# MCU_Control.net
KiCad netlist of a schematic drawn in Altium Designer
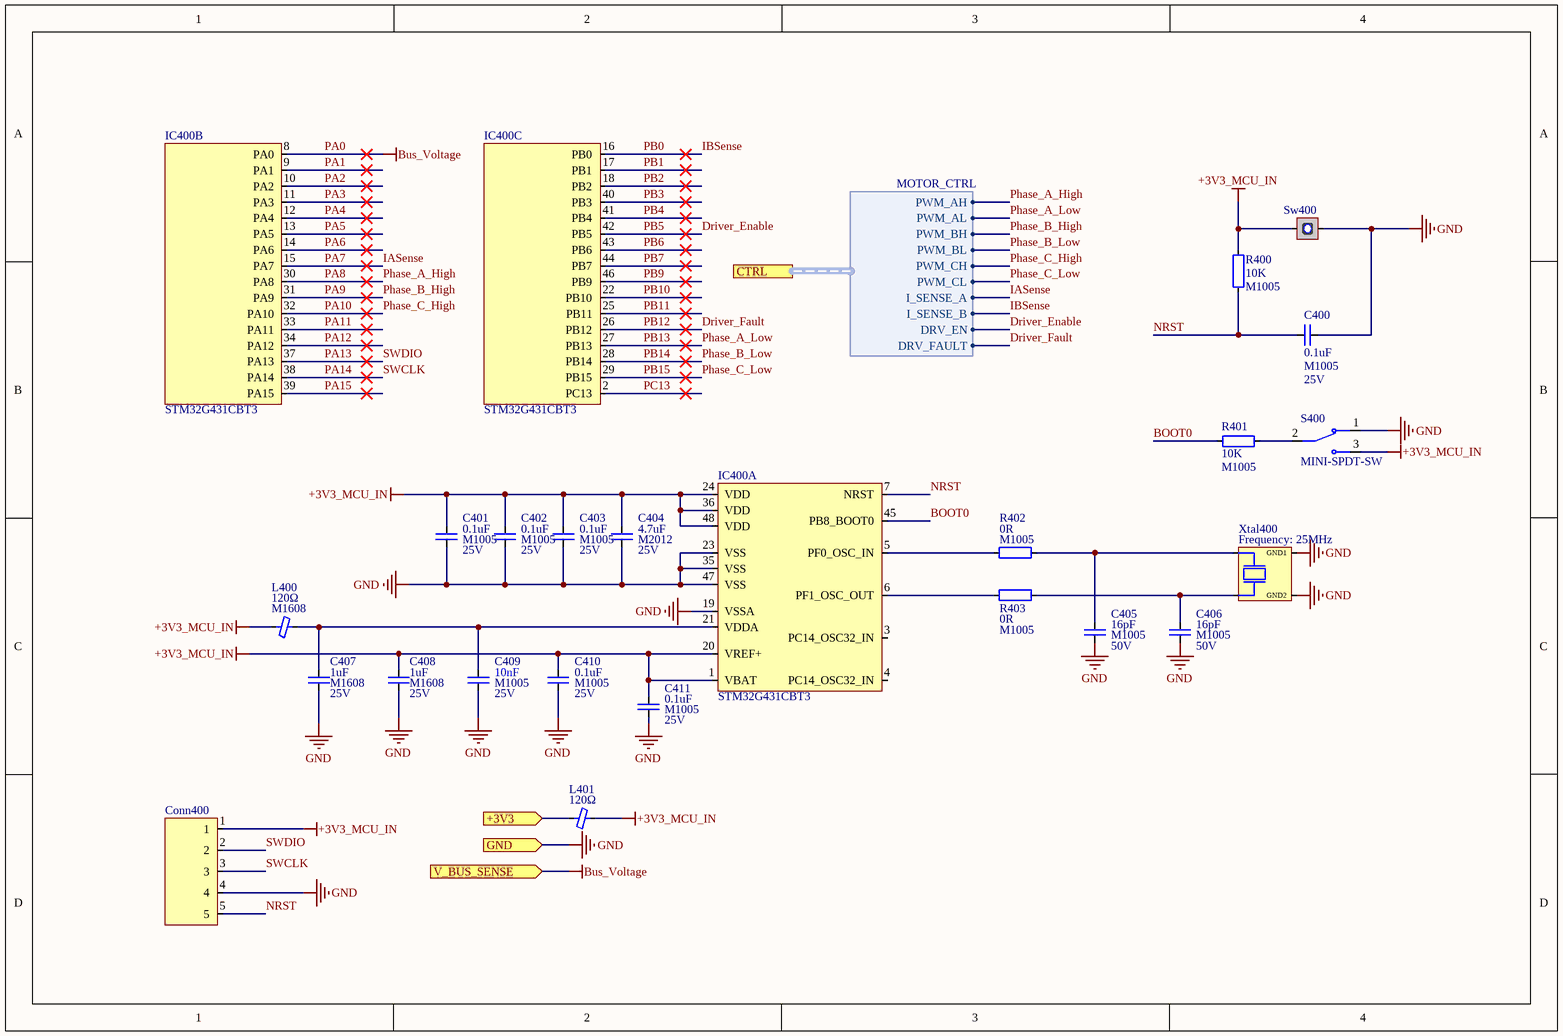
[diagram p0: MCU_Control.SchDoc]

(export (version "E")
  (design (tool "Eeschema 10.0.6"))
  (components
    (comp (ref "C400")
      (value "0.1uF")
      (footprint "Capacitor_Seramic_M1005_I0402")
      (description "Cap, Cer, 0.1uF, 25V, M1005")
      (fields
        (field (name "TOLERANCE") "±10%")
        (field (name "MANUFACTURER PART NUMBER") "CC0402KRX7R8BB104")
        (field (name "PACKAGE") "M1005")
        (field (name "RATED VOLTAGE") "25V")
      )
      (libsource (lib "Capacitor") (part "Capacitor_Seramic"))
    )
    (comp (ref "C401")
      (value "0.1uF")
      (footprint "Capacitor_Seramic_M1005_I0402")
      (description "Cap, Cer, 0.1uF, 25V, M1005")
      (fields
        (field (name "TOLERANCE") "±10%")
        (field (name "MANUFACTURER PART NUMBER") "CC0402KRX7R8BB104")
        (field (name "PACKAGE") "M1005")
        (field (name "RATED VOLTAGE") "25V")
      )
      (libsource (lib "Capacitor") (part "Capacitor_Seramic"))
    )
    (comp (ref "C402")
      (value "0.1uF")
      (footprint "Capacitor_Seramic_M1005_I0402")
      (description "Cap, Cer, 0.1uF, 25V, M1005")
      (fields
        (field (name "TOLERANCE") "±10%")
        (field (name "MANUFACTURER PART NUMBER") "CC0402KRX7R8BB104")
        (field (name "PACKAGE") "M1005")
        (field (name "RATED VOLTAGE") "25V")
      )
      (libsource (lib "Capacitor") (part "Capacitor_Seramic"))
    )
    (comp (ref "C403")
      (value "0.1uF")
      (footprint "Capacitor_Seramic_M1005_I0402")
      (description "Cap, Cer, 0.1uF, 25V, M1005")
      (fields
        (field (name "TOLERANCE") "±10%")
        (field (name "MANUFACTURER PART NUMBER") "CC0402KRX7R8BB104")
        (field (name "PACKAGE") "M1005")
        (field (name "RATED VOLTAGE") "25V")
      )
      (libsource (lib "Capacitor") (part "Capacitor_Seramic"))
    )
    (comp (ref "C404")
      (value "4.7uF")
      (footprint "Capacitor_Seramic_M2012_I0805")
      (description "Cap, Cer, 4.7uF, 25V, M2012")
      (fields
        (field (name "TOLERANCE") "±10%")
        (field (name "MANUFACTURER PART NUMBER") "C2012X7R1E475K125AB")
        (field (name "PACKAGE") "M2012")
        (field (name "RATED VOLTAGE") "25V")
      )
      (libsource (lib "Capacitor") (part "Capacitor_Seramic"))
    )
    (comp (ref "C405")
      (value "16pF")
      (footprint "Capacitor_Seramic_M1005_I0402")
      (description "Cap, Cer, 16pF, 50V, M1005")
      (fields
        (field (name "TOLERANCE") "5%")
        (field (name "MANUFACTURER PART NUMBER") "0402N160J500CT")
        (field (name "PACKAGE") "M1005")
        (field (name "RATED VOLTAGE") "50V")
      )
      (libsource (lib "Capacitor") (part "Capacitor_Seramic"))
    )
    (comp (ref "C406")
      (value "16pF")
      (footprint "Capacitor_Seramic_M1005_I0402")
      (description "Cap, Cer, 16pF, 50V, M1005")
      (fields
        (field (name "TOLERANCE") "5%")
        (field (name "MANUFACTURER PART NUMBER") "0402N160J500CT")
        (field (name "PACKAGE") "M1005")
        (field (name "RATED VOLTAGE") "50V")
      )
      (libsource (lib "Capacitor") (part "Capacitor_Seramic"))
    )
    (comp (ref "C407")
      (value "1uF")
      (footprint "Capacitor_Seramic_M1608_I0603")
      (description "Cap, Cer, 1uF, 25V, M1608")
      (fields
        (field (name "TOLERANCE") "±10%")
        (field (name "MANUFACTURER PART NUMBER") "C1608X7R1E105K080AB")
        (field (name "PACKAGE") "M1608")
        (field (name "RATED VOLTAGE") "25V")
      )
      (libsource (lib "Capacitor") (part "Capacitor_Seramic"))
    )
    (comp (ref "C408")
      (value "1uF")
      (footprint "Capacitor_Seramic_M1608_I0603")
      (description "Cap, Cer, 1uF, 25V, M1608")
      (fields
        (field (name "TOLERANCE") "±10%")
        (field (name "MANUFACTURER PART NUMBER") "C1608X7R1E105K080AB")
        (field (name "PACKAGE") "M1608")
        (field (name "RATED VOLTAGE") "25V")
      )
      (libsource (lib "Capacitor") (part "Capacitor_Seramic"))
    )
    (comp (ref "C409")
      (value "10nF")
      (footprint "Capacitor_Seramic_M1005_I0402")
      (description "Cap, Cer, 10nF, 25V, M1005")
      (fields
        (field (name "TOLERANCE") "±10%")
        (field (name "MANUFACTURER PART NUMBER") "CC0402KRX7R8BB103")
        (field (name "PACKAGE") "M1005")
        (field (name "RATED VOLTAGE") "25V")
      )
      (libsource (lib "Capacitor") (part "Capacitor_Seramic"))
    )
    (comp (ref "C410")
      (value "0.1uF")
      (footprint "Capacitor_Seramic_M1005_I0402")
      (description "Cap, Cer, 0.1uF, 25V, M1005")
      (fields
        (field (name "TOLERANCE") "±10%")
        (field (name "MANUFACTURER PART NUMBER") "CC0402KRX7R8BB104")
        (field (name "PACKAGE") "M1005")
        (field (name "RATED VOLTAGE") "25V")
      )
      (libsource (lib "Capacitor") (part "Capacitor_Seramic"))
    )
    (comp (ref "C411")
      (value "0.1uF")
      (footprint "Capacitor_Seramic_M1005_I0402")
      (description "Cap, Cer, 0.1uF, 25V, M1005")
      (fields
        (field (name "TOLERANCE") "±10%")
        (field (name "MANUFACTURER PART NUMBER") "CC0402KRX7R8BB104")
        (field (name "PACKAGE") "M1005")
        (field (name "RATED VOLTAGE") "25V")
      )
      (libsource (lib "Capacitor") (part "Capacitor_Seramic"))
    )
    (comp (ref "Conn400")
      (value "SM05B-GHS-TB(LF)(SN)")
      (footprint "Connector - JST, SM05B-GHS-TB")
      (description "Description")
      (fields
        (field (name "MANUFACTURER") "JST Sales America Inc.")
        (field (name "MANUFACTURER PART NUMBER") "SM05B-GHS-TB")
      )
      (libsource (lib "Connector - Header") (part "Connector - 5P"))
    )
    (comp (ref "IC400")
      (value "STM32G431CBT3")
      (footprint "QFP-48, 9mm x 9mm x 1.6mm")
      (libsource (lib "") (part "STM32G431CBT3_1"))
    )
    (comp (ref "L400")
      (value "120Ω")
      (footprint "Ferrite_Bead_Smd_M1608_I0603")
      (fields
        (field (name "MANUFACTURER PART NUMBER") "BLM18PG121SN1D")
        (field (name "MANUFACTURER") "Murata Electronics")
        (field (name "PACKAGE") "M1608")
        (field (name "Comment") "Ferrite Bead")
      )
      (libsource (lib "Inductor") (part "Ferrite Bead"))
    )
    (comp (ref "L401")
      (value "120Ω")
      (footprint "Ferrite_Bead_Smd_M1608_I0603")
      (fields
        (field (name "MANUFACTURER PART NUMBER") "BLM18PG121SN1D")
        (field (name "MANUFACTURER") "Murata Electronics")
        (field (name "Comment") "Ferrite Bead")
      )
      (libsource (lib "Inductor") (part "Ferrite Bead"))
    )
    (comp (ref "R400")
      (value "10K")
      (footprint "Resistor_SMD_M1005_I0402")
      (description "Res, 10K, 1%, M1005")
      (fields
        (field (name "MANUFACTURER") "Yageo")
        (field (name "MANUFACTURER PART NUMBER") "RC0402FR-0710KP")
        (field (name "PACKAGE") "M1005")
      )
      (libsource (lib "Resistor") (part "Resistor"))
    )
    (comp (ref "R401")
      (value "10K")
      (footprint "Resistor_SMD_M1005_I0402")
      (description "Res, 10K, 1%, M1005")
      (fields
        (field (name "MANUFACTURER") "Yageo")
        (field (name "MANUFACTURER PART NUMBER") "RC0402FR-0710KP")
        (field (name "PACKAGE") "M1005")
      )
      (libsource (lib "Resistor") (part "Resistor"))
    )
    (comp (ref "R402")
      (value "0R")
      (footprint "Resistor_SMD_M1005_I0402")
      (fields
        (field (name "MANUFACTURER") "Yageo")
        (field (name "MANUFACTURER PART NUMBER") "RC0402FR-070RL")
        (field (name "PACKAGE") "M1005")
        (field (name "Comment") "Resistor")
      )
      (libsource (lib "Resistor") (part "Resistor"))
    )
    (comp (ref "R403")
      (value "0R")
      (footprint "Resistor_SMD_M1005_I0402")
      (fields
        (field (name "MANUFACTURER") "Yageo")
        (field (name "MANUFACTURER PART NUMBER") "RC0402FR-070RL")
        (field (name "PACKAGE") "M1005")
        (field (name "Comment") "Resistor")
      )
      (libsource (lib "Resistor") (part "Resistor"))
    )
    (comp (ref "S400")
      (value "MINI-SPDT-SW")
      (footprint "MINI-SPDT-SW")
      (libsource (lib "Switch") (part "MINI-SPDT-SW"))
    )
    (comp (ref "Sw400")
      (value "Tactile, SPST")
      (footprint "Tactile, SPST - Panasonic, EVQQ2")
      (description "Switch, Tactile, SPST, SMD")
      (fields
        (field (name "MANUFACTURER") "Panasonic")
        (field (name "MANUFACTURER PART NUMBER") "EVQ-Q2K03W")
      )
      (libsource (lib "Switch") (part "Tactile, SPST"))
    )
    (comp (ref "Xtal400")
      (value "Crystal, Two Gnd Pins")
      (footprint "Kyocera, CX3225SB")
      (description "XTAL, 25MHz, 12pF")
      (fields
        (field (name "MANUFACTURER") "Kyocera")
        (field (name "MANUFACTURER PART NUMBER") "CX3225SB25000H0FLJCC")
        (field (name "FREQUENCY") "25MHz")
      )
      (libsource (lib "Crystal") (part "Crystal, Two Gnd Pins"))
    )
  )
  (nets
    (net (code "2") (name "+3V3_MCU_IN") (class "Default")
      (node (ref "C401") (pin "1") (pinfunction "1_1") (pintype "passive"))
      (node (ref "C402") (pin "1") (pinfunction "1_1") (pintype "passive"))
      (node (ref "C403") (pin "1") (pinfunction "1_1") (pintype "passive"))
      (node (ref "C404") (pin "1") (pinfunction "1_1") (pintype "passive"))
      (node (ref "C408") (pin "1") (pinfunction "1_1") (pintype "passive"))
      (node (ref "C410") (pin "1") (pinfunction "1_1") (pintype "passive"))
      (node (ref "C411") (pin "1") (pinfunction "1_1") (pintype "passive"))
      (node (ref "Conn400") (pin "1") (pinfunction "1_1") (pintype "passive"))
      (node (ref "IC400") (pin "1") (pinfunction "VBAT_1") (pintype "passive"))
      (node (ref "IC400") (pin "20") (pinfunction "VREF+_20") (pintype "passive"))
      (node (ref "IC400") (pin "24") (pinfunction "VDD_24") (pintype "passive"))
      (node (ref "IC400") (pin "36") (pinfunction "VDD_36") (pintype "passive"))
      (node (ref "IC400") (pin "48") (pinfunction "VDD_48") (pintype "passive"))
      (node (ref "L400") (pin "1") (pinfunction "1_1") (pintype "passive"))
      (node (ref "L401") (pin "2") (pinfunction "2_2") (pintype "passive"))
      (node (ref "R400") (pin "1") (pinfunction "1_1") (pintype "passive"))
      (node (ref "S400") (pin "3") (pinfunction "3_3") (pintype "passive"))
      (node (ref "Sw400") (pin "B") (pinfunction "B_B") (pintype "passive"))
    )
    (net (code "3") (name "/+3V3") (class "Default")
      (node (ref "L401") (pin "1") (pinfunction "1_1") (pintype "passive"))
    )
    (net (code "4") (name "/BOOT0") (class "Default")
      (node (ref "IC400") (pin "45") (pinfunction "PB8_BOOT0_45") (pintype "passive"))
      (node (ref "R401") (pin "2") (pinfunction "2_2") (pintype "passive"))
    )
    (net (code "5") (name "/Driver_Enable") (class "Default")
      (node (ref "IC400") (pin "42") (pinfunction "PB5_42") (pintype "passive"))
    )
    (net (code "6") (name "/Driver_Fault") (class "Default")
      (node (ref "IC400") (pin "26") (pinfunction "PB12_26") (pintype "passive"))
    )
    (net (code "7") (name "/IASense") (class "Default")
      (node (ref "IC400") (pin "15") (pinfunction "PA7_15") (pintype "passive"))
    )
    (net (code "8") (name "/IBSense") (class "Default")
      (node (ref "IC400") (pin "16") (pinfunction "PB0_16") (pintype "passive"))
    )
    (net (code "9") (name "/NRST") (class "Default")
      (node (ref "C400") (pin "2") (pinfunction "2_2") (pintype "passive"))
      (node (ref "Conn400") (pin "5") (pinfunction "5_5") (pintype "passive"))
      (node (ref "IC400") (pin "7") (pinfunction "NRST_7") (pintype "passive"))
      (node (ref "R400") (pin "2") (pinfunction "2_2") (pintype "passive"))
    )
    (net (code "10") (name "/PA1") (class "Default")
      (node (ref "IC400") (pin "9") (pinfunction "PA1_9") (pintype "passive"))
    )
    (net (code "11") (name "/PA2") (class "Default")
      (node (ref "IC400") (pin "10") (pinfunction "PA2_10") (pintype "passive"))
    )
    (net (code "12") (name "/PA3") (class "Default")
      (node (ref "IC400") (pin "11") (pinfunction "PA3_11") (pintype "passive"))
    )
    (net (code "13") (name "/PA4") (class "Default")
      (node (ref "IC400") (pin "12") (pinfunction "PA4_12") (pintype "passive"))
    )
    (net (code "14") (name "/PA5") (class "Default")
      (node (ref "IC400") (pin "13") (pinfunction "PA5_13") (pintype "passive"))
    )
    (net (code "15") (name "/PA6") (class "Default")
      (node (ref "IC400") (pin "14") (pinfunction "PA6_14") (pintype "passive"))
    )
    (net (code "16") (name "/PA8") (class "Default")
      (node (ref "IC400") (pin "30") (pinfunction "PA8_30") (pintype "passive"))
    )
    (net (code "17") (name "/PA9") (class "Default")
      (node (ref "IC400") (pin "31") (pinfunction "PA9_31") (pintype "passive"))
    )
    (net (code "18") (name "/PA10") (class "Default")
      (node (ref "IC400") (pin "32") (pinfunction "PA10_32") (pintype "passive"))
    )
    (net (code "19") (name "/PA11") (class "Default")
      (node (ref "IC400") (pin "33") (pinfunction "PA11_33") (pintype "passive"))
    )
    (net (code "20") (name "/PA12") (class "Default")
      (node (ref "IC400") (pin "34") (pinfunction "PA12_34") (pintype "passive"))
    )
    (net (code "21") (name "/PA13") (class "Default")
      (node (ref "Conn400") (pin "2") (pinfunction "2_2") (pintype "passive"))
      (node (ref "IC400") (pin "37") (pinfunction "PA13_37") (pintype "passive"))
    )
    (net (code "22") (name "/PA14") (class "Default")
      (node (ref "Conn400") (pin "3") (pinfunction "3_3") (pintype "passive"))
      (node (ref "IC400") (pin "38") (pinfunction "PA14_38") (pintype "passive"))
    )
    (net (code "23") (name "/PA15") (class "Default")
      (node (ref "IC400") (pin "39") (pinfunction "PA15_39") (pintype "passive"))
    )
    (net (code "24") (name "/PB1") (class "Default")
      (node (ref "IC400") (pin "17") (pinfunction "PB1_17") (pintype "passive"))
    )
    (net (code "25") (name "/PB2") (class "Default")
      (node (ref "IC400") (pin "18") (pinfunction "PB2_18") (pintype "passive"))
    )
    (net (code "26") (name "/PB3") (class "Default")
      (node (ref "IC400") (pin "40") (pinfunction "PB3_40") (pintype "passive"))
    )
    (net (code "27") (name "/PB4") (class "Default")
      (node (ref "IC400") (pin "41") (pinfunction "PB4_41") (pintype "passive"))
    )
    (net (code "28") (name "/PB6") (class "Default")
      (node (ref "IC400") (pin "43") (pinfunction "PB6_43") (pintype "passive"))
    )
    (net (code "29") (name "/PB7") (class "Default")
      (node (ref "IC400") (pin "44") (pinfunction "PB7_44") (pintype "passive"))
    )
    (net (code "30") (name "/PB9") (class "Default")
      (node (ref "IC400") (pin "46") (pinfunction "PB9_46") (pintype "passive"))
    )
    (net (code "31") (name "/PB10") (class "Default")
      (node (ref "IC400") (pin "22") (pinfunction "PB10_22") (pintype "passive"))
    )
    (net (code "32") (name "/PB11") (class "Default")
      (node (ref "IC400") (pin "25") (pinfunction "PB11_25") (pintype "passive"))
    )
    (net (code "33") (name "/PB13") (class "Default")
      (node (ref "IC400") (pin "27") (pinfunction "PB13_27") (pintype "passive"))
    )
    (net (code "34") (name "/PB14") (class "Default")
      (node (ref "IC400") (pin "28") (pinfunction "PB14_28") (pintype "passive"))
    )
    (net (code "35") (name "/PB15") (class "Default")
      (node (ref "IC400") (pin "29") (pinfunction "PB15_29") (pintype "passive"))
    )
    (net (code "36") (name "/PC13") (class "Default")
      (node (ref "IC400") (pin "2") (pinfunction "PC13_2") (pintype "passive"))
    )
    (net (code "38") (name "Bus_Voltage") (class "Default")
      (node (ref "IC400") (pin "8") (pinfunction "PA0_8") (pintype "passive"))
    )
    (net (code "39") (name "GND") (class "Default")
      (node (ref "C400") (pin "1") (pinfunction "1_1") (pintype "passive"))
      (node (ref "C401") (pin "2") (pinfunction "2_2") (pintype "passive"))
      (node (ref "C402") (pin "2") (pinfunction "2_2") (pintype "passive"))
      (node (ref "C403") (pin "2") (pinfunction "2_2") (pintype "passive"))
      (node (ref "C404") (pin "2") (pinfunction "2_2") (pintype "passive"))
      (node (ref "C405") (pin "2") (pinfunction "2_2") (pintype "passive"))
      (node (ref "C406") (pin "2") (pinfunction "2_2") (pintype "passive"))
      (node (ref "C407") (pin "2") (pinfunction "2_2") (pintype "passive"))
      (node (ref "C408") (pin "2") (pinfunction "2_2") (pintype "passive"))
      (node (ref "C409") (pin "2") (pinfunction "2_2") (pintype "passive"))
      (node (ref "C410") (pin "2") (pinfunction "2_2") (pintype "passive"))
      (node (ref "C411") (pin "2") (pinfunction "2_2") (pintype "passive"))
      (node (ref "Conn400") (pin "4") (pinfunction "4_4") (pintype "passive"))
      (node (ref "IC400") (pin "19") (pinfunction "VSSA_19") (pintype "passive"))
      (node (ref "IC400") (pin "23") (pinfunction "VSS_23") (pintype "passive"))
      (node (ref "IC400") (pin "35") (pinfunction "VSS_35") (pintype "passive"))
      (node (ref "IC400") (pin "47") (pinfunction "VSS_47") (pintype "passive"))
      (node (ref "S400") (pin "1") (pinfunction "1_1") (pintype "passive"))
      (node (ref "Sw400") (pin "A") (pinfunction "A_A") (pintype "passive"))
      (node (ref "Xtal400") (pin "GND1") (pinfunction "GND1_GND1") (pintype "passive"))
      (node (ref "Xtal400") (pin "GND2") (pinfunction "GND2_GND2") (pintype "passive"))
    )
    (net (code "40") (name "Net-(C405-Pad1)") (class "Default")
      (node (ref "C405") (pin "1") (pinfunction "1_1") (pintype "passive"))
      (node (ref "R402") (pin "2") (pinfunction "2_2") (pintype "passive"))
      (node (ref "Xtal400") (pin "2") (pinfunction "2_2") (pintype "passive"))
    )
    (net (code "41") (name "Net-(C406-Pad1)") (class "Default")
      (node (ref "C406") (pin "1") (pinfunction "1_1") (pintype "passive"))
      (node (ref "R403") (pin "2") (pinfunction "2_2") (pintype "passive"))
      (node (ref "Xtal400") (pin "1") (pinfunction "1_1") (pintype "passive"))
    )
    (net (code "42") (name "Net-(IC400A-PF0_OSC_IN)") (class "Default")
      (node (ref "IC400") (pin "5") (pinfunction "PF0_OSC_IN_5") (pintype "passive"))
      (node (ref "R402") (pin "1") (pinfunction "1_1") (pintype "passive"))
    )
    (net (code "43") (name "Net-(IC400A-PF1_OSC_OUT)") (class "Default")
      (node (ref "IC400") (pin "6") (pinfunction "PF1_OSC_OUT_6") (pintype "passive"))
      (node (ref "R403") (pin "1") (pinfunction "1_1") (pintype "passive"))
    )
    (net (code "44") (name "Net-(IC400A-VDDA)") (class "Default")
      (node (ref "C407") (pin "1") (pinfunction "1_1") (pintype "passive"))
      (node (ref "C409") (pin "1") (pinfunction "1_1") (pintype "passive"))
      (node (ref "IC400") (pin "21") (pinfunction "VDDA_21") (pintype "passive"))
      (node (ref "L400") (pin "2") (pinfunction "2_2") (pintype "passive"))
    )
    (net (code "45") (name "Net-(R401-Pad1)") (class "Default")
      (node (ref "R401") (pin "1") (pinfunction "1_1") (pintype "passive"))
      (node (ref "S400") (pin "2") (pinfunction "2_2") (pintype "passive"))
    )
    (net (code "46") (name "unconnected-(IC400A-PC14_OSC32_IN-Pad3)") (class "Default")
      (node (ref "IC400") (pin "3") (pinfunction "PC14_OSC32_IN_3") (pintype "passive"))
    )
    (net (code "47") (name "unconnected-(IC400A-PC14_OSC32_IN-Pad4)") (class "Default")
      (node (ref "IC400") (pin "4") (pinfunction "PC14_OSC32_IN_4") (pintype "passive"))
    )
  )
)
